# SCH_Portoise2_0_2024-07-28.net
KiCad netlist of a schematic drawn in EasyEDA
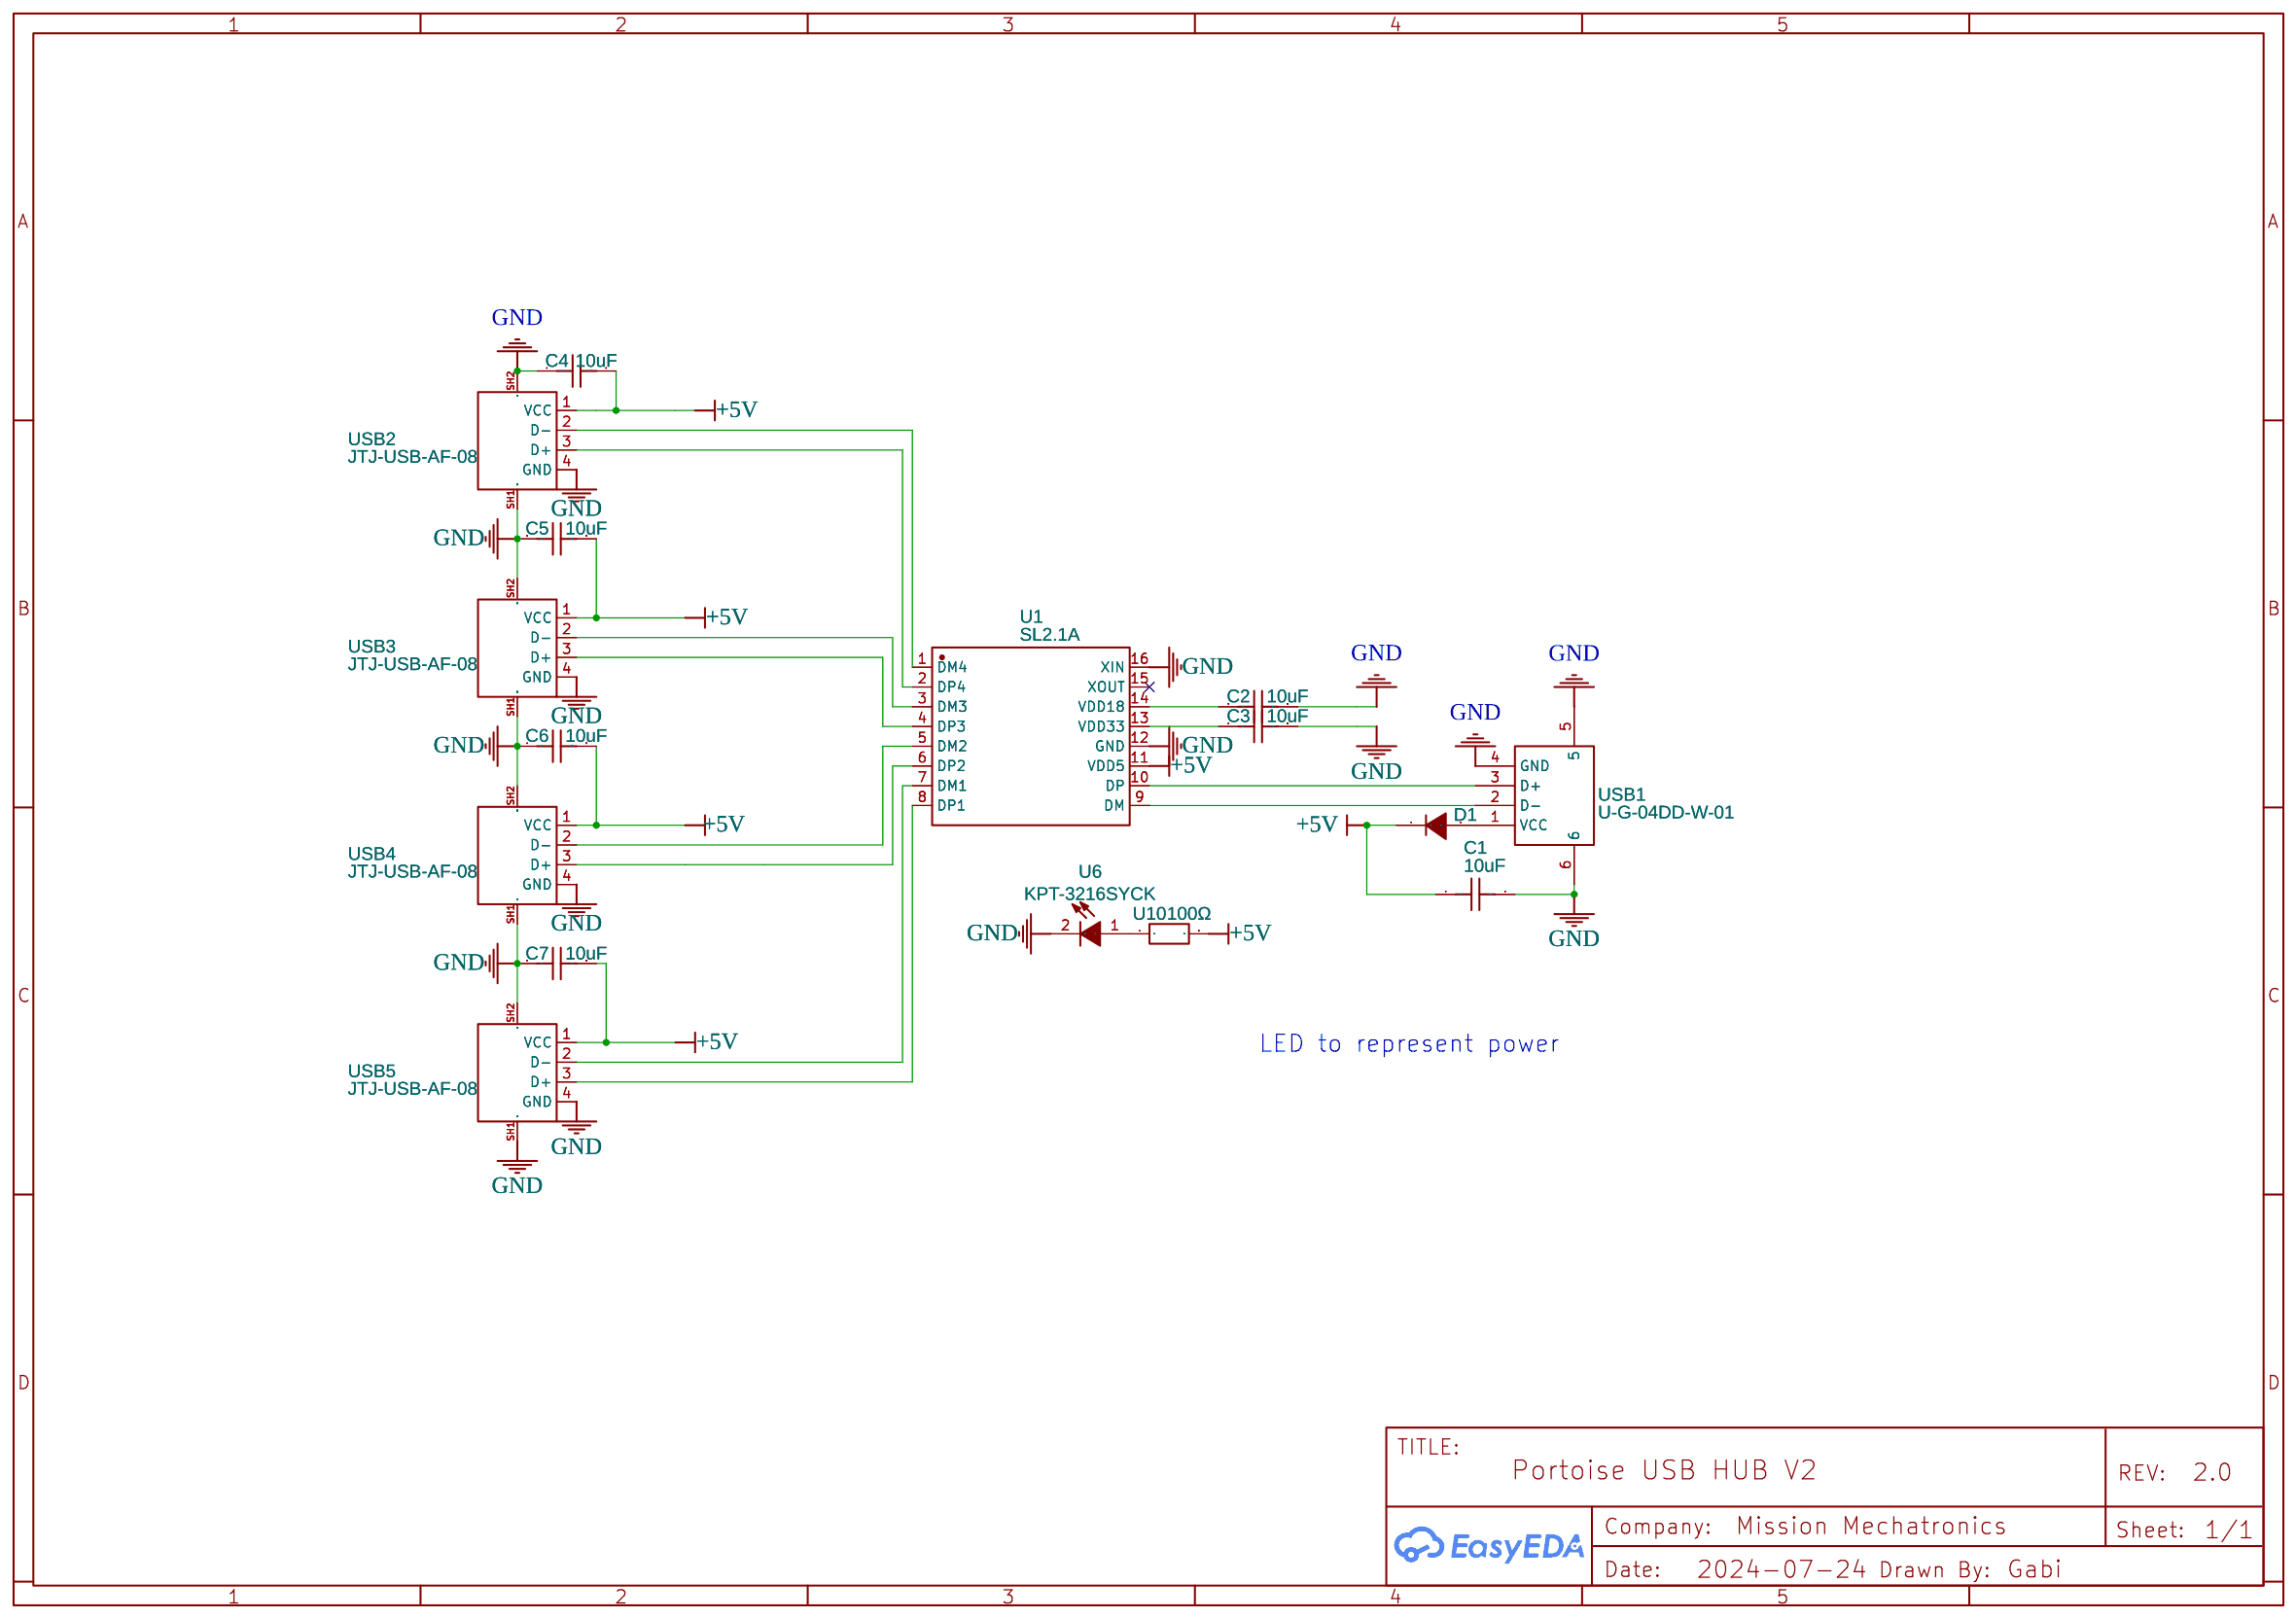
[diagram p0: schematic sheet]

(export (version "E")
  (design (tool "Eeschema 10.0.6"))
  (components
    (comp (ref "C1")
      (value "10uF")
      (fields
        (field (name "Manufacturer Part") "CL10A106KP8NNNC")
        (field (name "Manufacturer") "SAMSUNG(三星)")
      )
      (libsource (lib "") (part "CL10A106KP8NNNC"))
    )
    (comp (ref "C2")
      (value "10uF")
      (fields
        (field (name "Manufacturer Part") "CL10A106KP8NNNC")
        (field (name "Manufacturer") "SAMSUNG(三星)")
      )
      (libsource (lib "") (part "CL10A106KP8NNNC"))
    )
    (comp (ref "C3")
      (value "10uF")
      (fields
        (field (name "Manufacturer Part") "CL10A106KP8NNNC")
        (field (name "Manufacturer") "SAMSUNG(三星)")
      )
      (libsource (lib "") (part "CL10A106KP8NNNC"))
    )
    (comp (ref "C4")
      (value "10uF")
      (fields
        (field (name "Manufacturer Part") "CL10A106KP8NNNC")
        (field (name "Manufacturer") "SAMSUNG(三星)")
      )
      (libsource (lib "") (part "CL10A106KP8NNNC"))
    )
    (comp (ref "C5")
      (value "10uF")
      (fields
        (field (name "Manufacturer Part") "CL10A106KP8NNNC")
        (field (name "Manufacturer") "SAMSUNG(三星)")
      )
      (libsource (lib "") (part "CL10A106KP8NNNC"))
    )
    (comp (ref "C6")
      (value "10uF")
      (fields
        (field (name "Manufacturer Part") "CL10A106KP8NNNC")
        (field (name "Manufacturer") "SAMSUNG(三星)")
      )
      (libsource (lib "") (part "CL10A106KP8NNNC"))
    )
    (comp (ref "C7")
      (value "10uF")
      (fields
        (field (name "Manufacturer Part") "CL10A106KP8NNNC")
        (field (name "Manufacturer") "SAMSUNG(三星)")
      )
      (libsource (lib "") (part "CL10A106KP8NNNC"))
    )
    (comp (ref "D1")
      (value "NSR0320MW2T1G")
      (fields (field (name "Manufacturer") "onsemi(安森美)"))
      (libsource (lib "") (part "NSR0320MW2T1G"))
    )
    (comp (ref "U1")
      (value "SL2.1A")
      (fields (field (name "Manufacturer") "CoreChips(和芯润德)"))
      (libsource (lib "") (part "SL2.1A"))
    )
    (comp (ref "U6")
      (value "KPT-3216SYCK")
      (fields (field (name "Manufacturer") "Kingbright"))
      (libsource (lib "") (part "KPT-3216SYCK"))
    )
    (comp (ref "U10")
      (value "100Ω")
      (fields (field (name "Manufacturer Part") "OX101KE") (field (name "Manufacturer") "Ohmite"))
      (libsource (lib "") (part "OX101KE"))
    )
    (comp (ref "USB1")
      (value "U-G-04DD-W-01")
      (fields (field (name "Manufacturer Part") "U-G-O4DD-W-1") (field (name "Manufacturer") "韩国韩荣"))
      (libsource (lib "") (part "U-G-04DD-W-01"))
    )
    (comp (ref "USB2")
      (value "JTJ-USB-AF-08")
      (fields (field (name "Manufacturer Part") "902-131A1011D10100") (field (name "Manufacturer") "精拓金"))
      (libsource (lib "") (part "JTJ-USB-AF-08"))
    )
    (comp (ref "USB3")
      (value "JTJ-USB-AF-08")
      (fields (field (name "Manufacturer Part") "902-131A1011D10100") (field (name "Manufacturer") "精拓金"))
      (libsource (lib "") (part "JTJ-USB-AF-08"))
    )
    (comp (ref "USB4")
      (value "JTJ-USB-AF-08")
      (fields (field (name "Manufacturer Part") "902-131A1011D10100") (field (name "Manufacturer") "精拓金"))
      (libsource (lib "") (part "JTJ-USB-AF-08"))
    )
    (comp (ref "USB5")
      (value "JTJ-USB-AF-08")
      (fields (field (name "Manufacturer Part") "902-131A1011D10100") (field (name "Manufacturer") "精拓金"))
      (libsource (lib "") (part "JTJ-USB-AF-08"))
    )
  )
  (nets
    (net (code "1") (name "+5V") (class "Default")
      (node (ref "C1") (pin "1") (pinfunction "1_1") (pintype "unspecified"))
      (node (ref "C4") (pin "2") (pinfunction "2_2") (pintype "unspecified"))
      (node (ref "C5") (pin "2") (pinfunction "2_2") (pintype "unspecified"))
      (node (ref "C6") (pin "2") (pinfunction "2_2") (pintype "unspecified"))
      (node (ref "C7") (pin "2") (pinfunction "2_2") (pintype "unspecified"))
      (node (ref "D1") (pin "1") (pinfunction "C_1") (pintype "unspecified"))
      (node (ref "U1") (pin "11") (pinfunction "VDD5_11") (pintype "unspecified"))
      (node (ref "U10") (pin "2") (pinfunction "2_2") (pintype "unspecified"))
      (node (ref "USB2") (pin "1") (pinfunction "VCC_1") (pintype "input"))
      (node (ref "USB3") (pin "1") (pinfunction "VCC_1") (pintype "input"))
      (node (ref "USB4") (pin "1") (pinfunction "VCC_1") (pintype "input"))
      (node (ref "USB5") (pin "1") (pinfunction "VCC_1") (pintype "input"))
    )
    (net (code "2") (name "GND") (class "Default")
      (node (ref "C1") (pin "2") (pinfunction "2_2") (pintype "unspecified"))
      (node (ref "C2") (pin "2") (pinfunction "2_2") (pintype "unspecified"))
      (node (ref "C3") (pin "2") (pinfunction "2_2") (pintype "unspecified"))
      (node (ref "C4") (pin "1") (pinfunction "1_1") (pintype "unspecified"))
      (node (ref "C5") (pin "1") (pinfunction "1_1") (pintype "unspecified"))
      (node (ref "C6") (pin "1") (pinfunction "1_1") (pintype "unspecified"))
      (node (ref "C7") (pin "1") (pinfunction "1_1") (pintype "unspecified"))
      (node (ref "U1") (pin "12") (pinfunction "GND_12") (pintype "unspecified"))
      (node (ref "U1") (pin "16") (pinfunction "XIN_16") (pintype "unspecified"))
      (node (ref "U6") (pin "2") (pinfunction "C_2") (pintype "input"))
      (node (ref "USB1") (pin "4") (pinfunction "GND_4") (pintype "unspecified"))
      (node (ref "USB1") (pin "5") (pinfunction "5_5") (pintype "unspecified"))
      (node (ref "USB1") (pin "6") (pinfunction "6_6") (pintype "unspecified"))
      (node (ref "USB2") (pin "4") (pinfunction "GND_4") (pintype "input"))
      (node (ref "USB2") (pin "SH1") (pinfunction "SH1_SH1") (pintype "unspecified"))
      (node (ref "USB2") (pin "SH2") (pinfunction "SH2_SH2") (pintype "unspecified"))
      (node (ref "USB3") (pin "4") (pinfunction "GND_4") (pintype "input"))
      (node (ref "USB3") (pin "SH1") (pinfunction "SH1_SH1") (pintype "unspecified"))
      (node (ref "USB3") (pin "SH2") (pinfunction "SH2_SH2") (pintype "unspecified"))
      (node (ref "USB4") (pin "4") (pinfunction "GND_4") (pintype "input"))
      (node (ref "USB4") (pin "SH1") (pinfunction "SH1_SH1") (pintype "unspecified"))
      (node (ref "USB4") (pin "SH2") (pinfunction "SH2_SH2") (pintype "unspecified"))
      (node (ref "USB5") (pin "4") (pinfunction "GND_4") (pintype "input"))
      (node (ref "USB5") (pin "SH1") (pinfunction "SH1_SH1") (pintype "unspecified"))
      (node (ref "USB5") (pin "SH2") (pinfunction "SH2_SH2") (pintype "unspecified"))
    )
    (net (code "3") (name "Net-(D1-A)") (class "Default")
      (node (ref "D1") (pin "2") (pinfunction "A_2") (pintype "unspecified"))
      (node (ref "USB1") (pin "1") (pinfunction "VCC_1") (pintype "unspecified"))
    )
    (net (code "4") (name "Net-(U1-DM)") (class "Default")
      (node (ref "U1") (pin "9") (pinfunction "DM_9") (pintype "unspecified"))
      (node (ref "USB1") (pin "2") (pinfunction "D-_2") (pintype "unspecified"))
    )
    (net (code "5") (name "Net-(U1-DM1)") (class "Default")
      (node (ref "U1") (pin "7") (pinfunction "DM1_7") (pintype "unspecified"))
      (node (ref "USB5") (pin "2") (pinfunction "D-_2") (pintype "input"))
    )
    (net (code "6") (name "Net-(U1-DM2)") (class "Default")
      (node (ref "U1") (pin "5") (pinfunction "DM2_5") (pintype "unspecified"))
      (node (ref "USB4") (pin "2") (pinfunction "D-_2") (pintype "input"))
    )
    (net (code "7") (name "Net-(U1-DM3)") (class "Default")
      (node (ref "U1") (pin "3") (pinfunction "DM3_3") (pintype "unspecified"))
      (node (ref "USB3") (pin "2") (pinfunction "D-_2") (pintype "input"))
    )
    (net (code "8") (name "Net-(U1-DM4)") (class "Default")
      (node (ref "U1") (pin "1") (pinfunction "DM4_1") (pintype "unspecified"))
      (node (ref "USB2") (pin "2") (pinfunction "D-_2") (pintype "input"))
    )
    (net (code "9") (name "Net-(U1-DP)") (class "Default")
      (node (ref "U1") (pin "10") (pinfunction "DP_10") (pintype "unspecified"))
      (node (ref "USB1") (pin "3") (pinfunction "D+_3") (pintype "unspecified"))
    )
    (net (code "10") (name "Net-(U1-DP1)") (class "Default")
      (node (ref "U1") (pin "8") (pinfunction "DP1_8") (pintype "unspecified"))
      (node (ref "USB5") (pin "3") (pinfunction "D+_3") (pintype "input"))
    )
    (net (code "11") (name "Net-(U1-DP2)") (class "Default")
      (node (ref "U1") (pin "6") (pinfunction "DP2_6") (pintype "unspecified"))
      (node (ref "USB4") (pin "3") (pinfunction "D+_3") (pintype "input"))
    )
    (net (code "12") (name "Net-(U1-DP3)") (class "Default")
      (node (ref "U1") (pin "4") (pinfunction "DP3_4") (pintype "unspecified"))
      (node (ref "USB3") (pin "3") (pinfunction "D+_3") (pintype "input"))
    )
    (net (code "13") (name "Net-(U1-DP4)") (class "Default")
      (node (ref "U1") (pin "2") (pinfunction "DP4_2") (pintype "unspecified"))
      (node (ref "USB2") (pin "3") (pinfunction "D+_3") (pintype "input"))
    )
    (net (code "14") (name "Net-(U1-VDD18)") (class "Default")
      (node (ref "C2") (pin "1") (pinfunction "1_1") (pintype "unspecified"))
      (node (ref "U1") (pin "14") (pinfunction "VDD18_14") (pintype "unspecified"))
    )
    (net (code "15") (name "Net-(U1-VDD33)") (class "Default")
      (node (ref "C3") (pin "1") (pinfunction "1_1") (pintype "unspecified"))
      (node (ref "U1") (pin "13") (pinfunction "VDD33_13") (pintype "unspecified"))
    )
    (net (code "16") (name "Net-(U6-A)") (class "Default")
      (node (ref "U10") (pin "1") (pinfunction "1_1") (pintype "unspecified"))
      (node (ref "U6") (pin "1") (pinfunction "A_1") (pintype "input"))
    )
    (net (code "17") (name "unconnected-(U1-XOUT-Pad15)") (class "Default")
      (node (ref "U1") (pin "15") (pinfunction "XOUT_15") (pintype "unspecified+no_connect"))
    )
  )
)
